# uC.net
KiCad netlist of a schematic drawn in Altium Designer
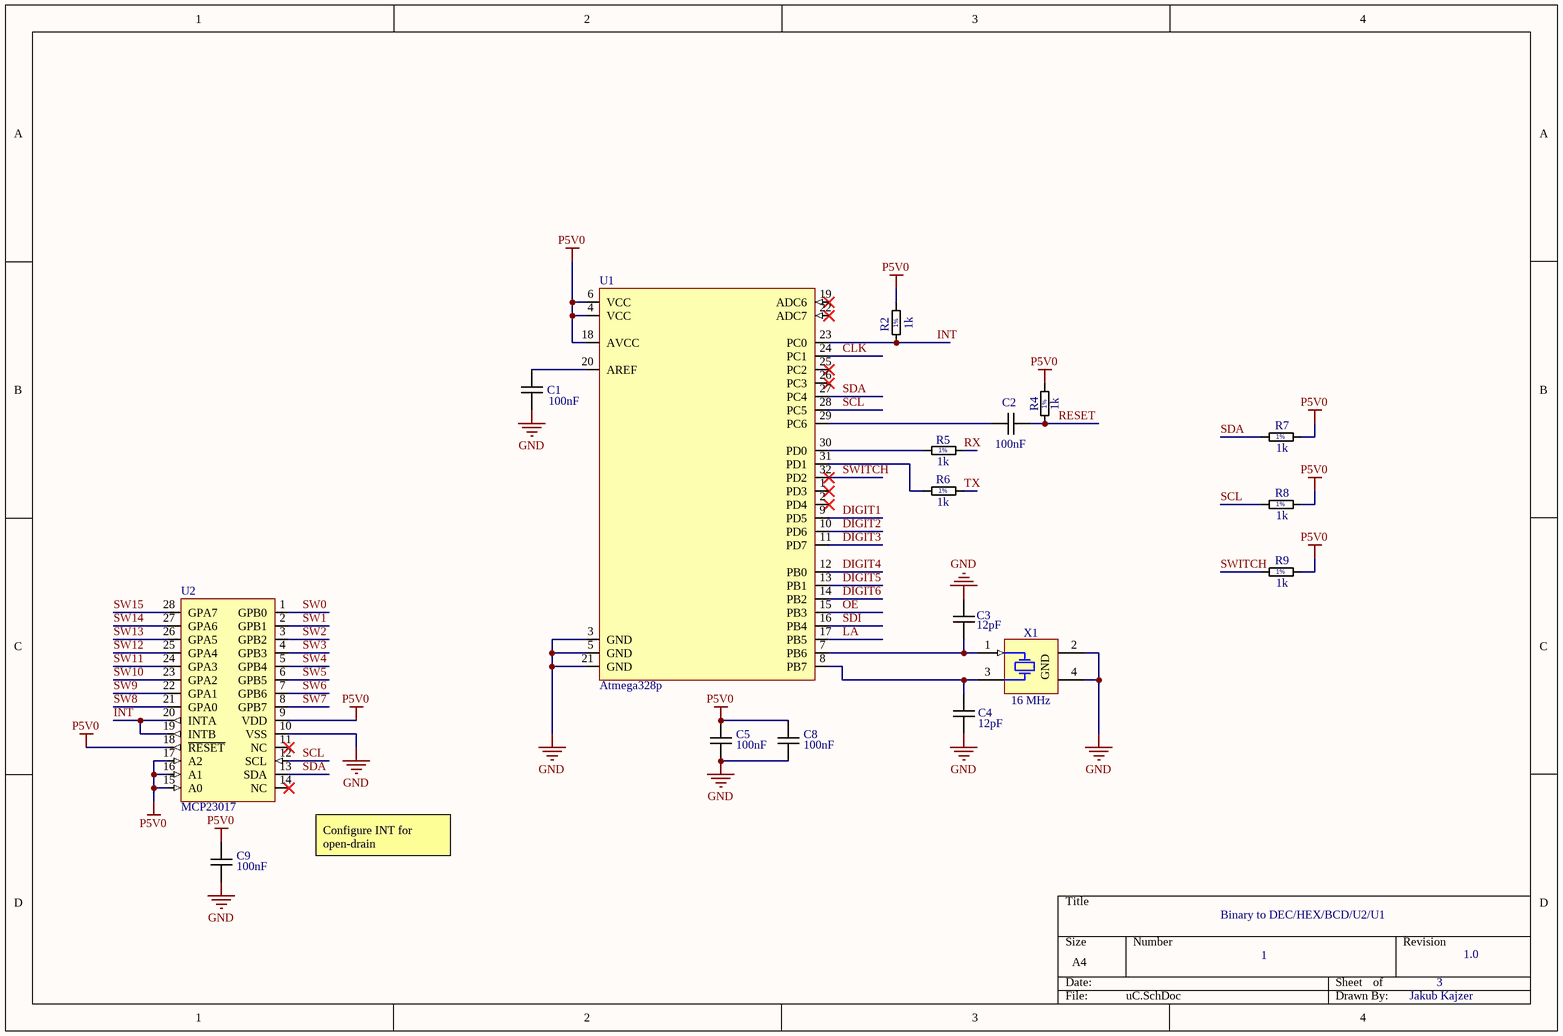
[diagram p0: uC.SchDoc]

(export (version "E")
  (design (tool "Eeschema 10.0.6"))
  (components
    (comp (ref "C1")
      (value "100nF")
      (footprint "CAPC0402X60N")
      (description "Non-polarised capacitor")
      (fields
        (field (name "MANUFACTURER") "GENERIC")
        (field (name "MANUFACTURER PART NUMBER") "CC0402_100NF_16V_10%_X7R")
        (field (name "AUTHOR") "KB")
      )
      (libsource (lib "Capacitors") (part "Capacitor - non polarized"))
    )
    (comp (ref "C2")
      (value "100nF")
      (footprint "CAPC0402X60N")
      (description "Non-polarised capacitor")
      (fields
        (field (name "MANUFACTURER") "GENERIC")
        (field (name "MANUFACTURER PART NUMBER") "CC0402_100NF_16V_10%_X7R")
        (field (name "AUTHOR") "KB")
      )
      (libsource (lib "Capacitors") (part "Capacitor - non polarized"))
    )
    (comp (ref "C3")
      (value "12pF")
      (footprint "CAPC0402X60N")
      (description "Non-polarised capacitor")
      (fields
        (field (name "MANUFACTURER") "GENERIC")
        (field (name "MANUFACTURER PART NUMBER") "CC0402_12PF_50V_5%_C0G")
        (field (name "AUTHOR") "KB")
      )
      (libsource (lib "Capacitors") (part "Capacitor - non polarized"))
    )
    (comp (ref "C4")
      (value "12pF")
      (footprint "CAPC0402X60N")
      (description "Non-polarised capacitor")
      (fields
        (field (name "MANUFACTURER") "GENERIC")
        (field (name "MANUFACTURER PART NUMBER") "CC0402_12PF_50V_5%_C0G")
        (field (name "AUTHOR") "KB")
      )
      (libsource (lib "Capacitors") (part "Capacitor - non polarized"))
    )
    (comp (ref "C5")
      (value "100nF")
      (footprint "CAPC0402X60N")
      (description "Non-polarised capacitor")
      (fields
        (field (name "MANUFACTURER") "GENERIC")
        (field (name "MANUFACTURER PART NUMBER") "CC0402_100NF_16V_10%_X7R")
        (field (name "AUTHOR") "KB")
      )
      (libsource (lib "Capacitors") (part "Capacitor - non polarized"))
    )
    (comp (ref "C8")
      (value "100nF")
      (footprint "CAPC0402X60N")
      (description "Non-polarised capacitor")
      (fields
        (field (name "MANUFACTURER") "GENERIC")
        (field (name "MANUFACTURER PART NUMBER") "CC0402_100NF_16V_10%_X7R")
        (field (name "AUTHOR") "KB")
      )
      (libsource (lib "Capacitors") (part "Capacitor - non polarized"))
    )
    (comp (ref "C9")
      (value "100nF")
      (footprint "CAPC0402X60N")
      (description "Non-polarised capacitor")
      (fields
        (field (name "MANUFACTURER") "GENERIC")
        (field (name "MANUFACTURER PART NUMBER") "CC0402_100NF_16V_10%_X7R")
        (field (name "AUTHOR") "KB")
      )
      (libsource (lib "Capacitors") (part "Capacitor - non polarized"))
    )
    (comp (ref "R2")
      (value "1k")
      (footprint "RESC0402X40N")
      (description "General Purpose Thick Film Chip Resistor")
      (fields
        (field (name "MANUFACTURER") "GENERIC")
        (field (name "MANUFACTURER PART NUMBER") "R0402_1K00_0.0625W 0.1W 0.125W 0.25W 0.5W 1W 0.75W 1W_100PPM")
        (field (name "AUTHOR") "KB")
      )
      (libsource (lib "Resistors") (part "Resistor - 1%"))
    )
    (comp (ref "R4")
      (value "1k")
      (footprint "RESC0402X40N")
      (description "General Purpose Thick Film Chip Resistor")
      (fields
        (field (name "MANUFACTURER") "GENERIC")
        (field (name "MANUFACTURER PART NUMBER") "R0402_1K00_0.0625W 0.1W 0.125W 0.25W 0.5W 1W 0.75W 1W_100PPM")
        (field (name "AUTHOR") "KB")
      )
      (libsource (lib "Resistors") (part "Resistor - 1%"))
    )
    (comp (ref "R5")
      (value "1k")
      (footprint "RESC0402X40N")
      (description "General Purpose Thick Film Chip Resistor")
      (fields
        (field (name "MANUFACTURER") "GENERIC")
        (field (name "MANUFACTURER PART NUMBER") "R0402_1K00_0.0625W 0.1W 0.125W 0.25W 0.5W 1W 0.75W 1W_100PPM")
        (field (name "AUTHOR") "KB")
      )
      (libsource (lib "Resistors") (part "Resistor - 1%"))
    )
    (comp (ref "R6")
      (value "1k")
      (footprint "RESC0402X40N")
      (description "General Purpose Thick Film Chip Resistor")
      (fields
        (field (name "MANUFACTURER") "GENERIC")
        (field (name "MANUFACTURER PART NUMBER") "R0402_1K00_0.0625W 0.1W 0.125W 0.25W 0.5W 1W 0.75W 1W_100PPM")
        (field (name "AUTHOR") "KB")
      )
      (libsource (lib "Resistors") (part "Resistor - 1%"))
    )
    (comp (ref "R7")
      (value "1k")
      (footprint "RESC0402X40N")
      (description "General Purpose Thick Film Chip Resistor")
      (fields
        (field (name "MANUFACTURER") "GENERIC")
        (field (name "MANUFACTURER PART NUMBER") "R0402_1K00_0.0625W 0.1W 0.125W 0.25W 0.5W 1W 0.75W 1W_100PPM")
        (field (name "AUTHOR") "KB")
      )
      (libsource (lib "Resistors") (part "Resistor - 1%"))
    )
    (comp (ref "R8")
      (value "1k")
      (footprint "RESC0402X40N")
      (description "General Purpose Thick Film Chip Resistor")
      (fields
        (field (name "MANUFACTURER") "GENERIC")
        (field (name "MANUFACTURER PART NUMBER") "R0402_1K00_0.0625W 0.1W 0.125W 0.25W 0.5W 1W 0.75W 1W_100PPM")
        (field (name "AUTHOR") "KB")
      )
      (libsource (lib "Resistors") (part "Resistor - 1%"))
    )
    (comp (ref "R9")
      (value "1k")
      (footprint "RESC0402X40N")
      (description "General Purpose Thick Film Chip Resistor")
      (fields
        (field (name "MANUFACTURER") "GENERIC")
        (field (name "MANUFACTURER PART NUMBER") "R0402_1K00_0.0625W 0.1W 0.125W 0.25W 0.5W 1W 0.75W 1W_100PPM")
        (field (name "AUTHOR") "KB")
      )
      (libsource (lib "Resistors") (part "Resistor - 1%"))
    )
    (comp (ref "U1")
      (value "Atmega328p")
      (footprint "STM-LQFP32_N")
      (description "8-bit AVR Microcontroller with 32K Bytes In-SystemProgrammable Flash")
      (fields (field (name "MANUFACTURER 1 PART NUMBER") "ATMEGA328PB-AU") (field (name "AUTHOR") "JK"))
      (libsource (lib "ICs And Semiconductors") (part "Atmega328p"))
    )
    (comp (ref "U2")
      (value "MCP23017")
      (footprint "SSOP28")
      (description "16-Bit I/O Expander with Serial Interface")
      (fields (field (name "MANUFACTURER 1 PART NUMBER") "MCP23017-E/SS") (field (name "AUTHOR") "JK"))
      (libsource (lib "ICs And Semiconductors") (part "MCP23017"))
    )
    (comp (ref "X1")
      (value "16 MHz")
      (footprint "LFXTAL069392CUTT")
      (description "ˇĹ0ppm 10pF -40°C to +85°C  4 Pins, 2.5x2X0.6mm")
      (fields (field (name "MANUFACTURER 1 PART NUMBER") "LFXTAL069392CUTT") (field (name "AUTHOR") "PC"))
      (libsource (lib "ICs And Semiconductors") (part "Quartz Crystal 1X 2GND 3X 4GND"))
    )
  )
  (nets
    (net (code "1") (name "/CLK") (class "Default")
      (node (ref "U1") (pin "24") (pinfunction "PC1_24") (pintype "bidirectional"))
    )
    (net (code "2") (name "/DIGIT1") (class "Default")
      (node (ref "U1") (pin "9") (pinfunction "PD5_9") (pintype "bidirectional"))
    )
    (net (code "3") (name "/DIGIT2") (class "Default")
      (node (ref "U1") (pin "10") (pinfunction "PD6_10") (pintype "bidirectional"))
    )
    (net (code "4") (name "/DIGIT3") (class "Default")
      (node (ref "U1") (pin "11") (pinfunction "PD7_11") (pintype "bidirectional"))
    )
    (net (code "5") (name "/DIGIT4") (class "Default")
      (node (ref "U1") (pin "12") (pinfunction "PB0_12") (pintype "bidirectional"))
    )
    (net (code "6") (name "/DIGIT5") (class "Default")
      (node (ref "U1") (pin "13") (pinfunction "PB1_13") (pintype "bidirectional"))
    )
    (net (code "7") (name "/DIGIT6") (class "Default")
      (node (ref "U1") (pin "14") (pinfunction "PB2_14") (pintype "bidirectional"))
    )
    (net (code "8") (name "/INT") (class "Default")
      (node (ref "R2") (pin "1") (pinfunction "1_1") (pintype "passive"))
      (node (ref "U1") (pin "23") (pinfunction "PC0_23") (pintype "bidirectional"))
      (node (ref "U2") (pin "19") (pinfunction "INTB_19") (pintype "output"))
      (node (ref "U2") (pin "20") (pinfunction "INTA_20") (pintype "output"))
    )
    (net (code "9") (name "/LA") (class "Default")
      (node (ref "U1") (pin "17") (pinfunction "PB5_17") (pintype "bidirectional"))
    )
    (net (code "10") (name "/OE") (class "Default")
      (node (ref "U1") (pin "15") (pinfunction "PB3_15") (pintype "bidirectional"))
    )
    (net (code "11") (name "/RESET") (class "Default")
      (node (ref "C2") (pin "2") (pinfunction "2_2") (pintype "passive"))
      (node (ref "R4") (pin "1") (pinfunction "1_1") (pintype "passive"))
    )
    (net (code "12") (name "/RX") (class "Default")
      (node (ref "R5") (pin "2") (pinfunction "2_2") (pintype "passive"))
    )
    (net (code "13") (name "/SCL") (class "Default")
      (node (ref "R8") (pin "1") (pinfunction "1_1") (pintype "passive"))
      (node (ref "U1") (pin "28") (pinfunction "PC5_28") (pintype "bidirectional"))
      (node (ref "U2") (pin "12") (pinfunction "SCL_12") (pintype "input"))
    )
    (net (code "14") (name "/SDA") (class "Default")
      (node (ref "R7") (pin "1") (pinfunction "1_1") (pintype "passive"))
      (node (ref "U1") (pin "27") (pinfunction "PC4_27") (pintype "bidirectional"))
      (node (ref "U2") (pin "13") (pinfunction "SDA_13") (pintype "bidirectional"))
    )
    (net (code "15") (name "/SDI") (class "Default")
      (node (ref "U1") (pin "16") (pinfunction "PB4_16") (pintype "bidirectional"))
    )
    (net (code "16") (name "/SW0") (class "Default")
      (node (ref "U2") (pin "1") (pinfunction "GPB0_1") (pintype "bidirectional"))
    )
    (net (code "17") (name "/SW1") (class "Default")
      (node (ref "U2") (pin "2") (pinfunction "GPB1_2") (pintype "bidirectional"))
    )
    (net (code "18") (name "/SW2") (class "Default")
      (node (ref "U2") (pin "3") (pinfunction "GPB2_3") (pintype "bidirectional"))
    )
    (net (code "19") (name "/SW3") (class "Default")
      (node (ref "U2") (pin "4") (pinfunction "GPB3_4") (pintype "bidirectional"))
    )
    (net (code "20") (name "/SW4") (class "Default")
      (node (ref "U2") (pin "5") (pinfunction "GPB4_5") (pintype "bidirectional"))
    )
    (net (code "21") (name "/SW5") (class "Default")
      (node (ref "U2") (pin "6") (pinfunction "GPB5_6") (pintype "bidirectional"))
    )
    (net (code "22") (name "/SW6") (class "Default")
      (node (ref "U2") (pin "7") (pinfunction "GPB6_7") (pintype "bidirectional"))
    )
    (net (code "23") (name "/SW7") (class "Default")
      (node (ref "U2") (pin "8") (pinfunction "GPB7_8") (pintype "bidirectional"))
    )
    (net (code "24") (name "/SW8") (class "Default")
      (node (ref "U2") (pin "21") (pinfunction "GPA0_21") (pintype "bidirectional"))
    )
    (net (code "25") (name "/SW9") (class "Default")
      (node (ref "U2") (pin "22") (pinfunction "GPA1_22") (pintype "bidirectional"))
    )
    (net (code "26") (name "/SW10") (class "Default")
      (node (ref "U2") (pin "23") (pinfunction "GPA2_23") (pintype "bidirectional"))
    )
    (net (code "27") (name "/SW11") (class "Default")
      (node (ref "U2") (pin "24") (pinfunction "GPA3_24") (pintype "bidirectional"))
    )
    (net (code "28") (name "/SW12") (class "Default")
      (node (ref "U2") (pin "25") (pinfunction "GPA4_25") (pintype "bidirectional"))
    )
    (net (code "29") (name "/SW13") (class "Default")
      (node (ref "U2") (pin "26") (pinfunction "GPA5_26") (pintype "bidirectional"))
    )
    (net (code "30") (name "/SW14") (class "Default")
      (node (ref "U2") (pin "27") (pinfunction "GPA6_27") (pintype "bidirectional"))
    )
    (net (code "31") (name "/SW15") (class "Default")
      (node (ref "U2") (pin "28") (pinfunction "GPA7_28") (pintype "bidirectional"))
    )
    (net (code "32") (name "/SWITCH") (class "Default")
      (node (ref "R9") (pin "1") (pinfunction "1_1") (pintype "passive"))
      (node (ref "U1") (pin "32") (pinfunction "PD2_32") (pintype "bidirectional"))
    )
    (net (code "33") (name "/TX") (class "Default")
      (node (ref "R6") (pin "2") (pinfunction "2_2") (pintype "passive"))
    )
    (net (code "34") (name "GND") (class "Default")
      (node (ref "C1") (pin "1") (pinfunction "1_1") (pintype "passive"))
      (node (ref "C3") (pin "2") (pinfunction "2_2") (pintype "passive"))
      (node (ref "C4") (pin "1") (pinfunction "1_1") (pintype "passive"))
      (node (ref "C5") (pin "1") (pinfunction "1_1") (pintype "passive"))
      (node (ref "C8") (pin "1") (pinfunction "1_1") (pintype "passive"))
      (node (ref "C9") (pin "1") (pinfunction "1_1") (pintype "passive"))
      (node (ref "U1") (pin "21") (pinfunction "GND_21") (pintype "power_in"))
      (node (ref "U1") (pin "3") (pinfunction "GND_3") (pintype "power_in"))
      (node (ref "U1") (pin "5") (pinfunction "GND_5") (pintype "power_in"))
      (node (ref "U2") (pin "10") (pinfunction "VSS_10") (pintype "power_in"))
      (node (ref "X1") (pin "2") (pinfunction "GND_2") (pintype "power_in"))
      (node (ref "X1") (pin "4") (pinfunction "GND_4") (pintype "power_in"))
    )
    (net (code "35") (name "Net-(U1-AREF)") (class "Default")
      (node (ref "C1") (pin "2") (pinfunction "2_2") (pintype "passive"))
      (node (ref "U1") (pin "20") (pinfunction "AREF_20") (pintype "power_in"))
    )
    (net (code "36") (name "Net-(U1-PB6)") (class "Default")
      (node (ref "C3") (pin "1") (pinfunction "1_1") (pintype "passive"))
      (node (ref "U1") (pin "7") (pinfunction "PB6_7") (pintype "bidirectional"))
      (node (ref "X1") (pin "1") (pinfunction "X_1") (pintype "input"))
    )
    (net (code "37") (name "Net-(U1-PB7)") (class "Default")
      (node (ref "C4") (pin "2") (pinfunction "2_2") (pintype "passive"))
      (node (ref "U1") (pin "8") (pinfunction "PB7_8") (pintype "bidirectional"))
      (node (ref "X1") (pin "3") (pinfunction "X_3") (pintype "power_in"))
    )
    (net (code "38") (name "Net-(U1-PC6)") (class "Default")
      (node (ref "C2") (pin "1") (pinfunction "1_1") (pintype "passive"))
      (node (ref "U1") (pin "29") (pinfunction "PC6_29") (pintype "bidirectional"))
    )
    (net (code "39") (name "Net-(U1-PD0)") (class "Default")
      (node (ref "R5") (pin "1") (pinfunction "1_1") (pintype "passive"))
      (node (ref "U1") (pin "30") (pinfunction "PD0_30") (pintype "bidirectional"))
    )
    (net (code "40") (name "Net-(U1-PD1)") (class "Default")
      (node (ref "R6") (pin "1") (pinfunction "1_1") (pintype "passive"))
      (node (ref "U1") (pin "31") (pinfunction "PD1_31") (pintype "bidirectional"))
    )
    (net (code "41") (name "P5V0") (class "Default")
      (node (ref "C5") (pin "2") (pinfunction "2_2") (pintype "passive"))
      (node (ref "C8") (pin "2") (pinfunction "2_2") (pintype "passive"))
      (node (ref "C9") (pin "2") (pinfunction "2_2") (pintype "passive"))
      (node (ref "R2") (pin "2") (pinfunction "2_2") (pintype "passive"))
      (node (ref "R4") (pin "2") (pinfunction "2_2") (pintype "passive"))
      (node (ref "R7") (pin "2") (pinfunction "2_2") (pintype "passive"))
      (node (ref "R8") (pin "2") (pinfunction "2_2") (pintype "passive"))
      (node (ref "R9") (pin "2") (pinfunction "2_2") (pintype "passive"))
      (node (ref "U1") (pin "18") (pinfunction "AVCC_18") (pintype "power_in"))
      (node (ref "U1") (pin "4") (pinfunction "VCC_4") (pintype "power_in"))
      (node (ref "U1") (pin "6") (pinfunction "VCC_6") (pintype "power_in"))
      (node (ref "U2") (pin "15") (pinfunction "A0_15") (pintype "input"))
      (node (ref "U2") (pin "16") (pinfunction "A1_16") (pintype "input"))
      (node (ref "U2") (pin "17") (pinfunction "A2_17") (pintype "input"))
      (node (ref "U2") (pin "18") (pinfunction "~{RESET}_18") (pintype "output"))
      (node (ref "U2") (pin "9") (pinfunction "VDD_9") (pintype "power_in"))
    )
    (net (code "42") (name "unconnected-(U1-ADC6-Pad19)") (class "Default")
      (node (ref "U1") (pin "19") (pinfunction "ADC6_19") (pintype "input+no_connect"))
    )
    (net (code "43") (name "unconnected-(U1-ADC7-Pad22)") (class "Default")
      (node (ref "U1") (pin "22") (pinfunction "ADC7_22") (pintype "input+no_connect"))
    )
    (net (code "44") (name "unconnected-(U1-PC2-Pad25)") (class "Default")
      (node (ref "U1") (pin "25") (pinfunction "PC2_25") (pintype "bidirectional+no_connect"))
    )
    (net (code "45") (name "unconnected-(U1-PC3-Pad26)") (class "Default")
      (node (ref "U1") (pin "26") (pinfunction "PC3_26") (pintype "bidirectional+no_connect"))
    )
    (net (code "46") (name "unconnected-(U1-PD3-Pad1)") (class "Default")
      (node (ref "U1") (pin "1") (pinfunction "PD3_1") (pintype "bidirectional+no_connect"))
    )
    (net (code "47") (name "unconnected-(U1-PD4-Pad2)") (class "Default")
      (node (ref "U1") (pin "2") (pinfunction "PD4_2") (pintype "bidirectional+no_connect"))
    )
    (net (code "48") (name "unconnected-(U2-NC-Pad11)") (class "Default")
      (node (ref "U2") (pin "11") (pinfunction "NC_11") (pintype "passive+no_connect"))
    )
    (net (code "49") (name "unconnected-(U2-NC-Pad14)") (class "Default")
      (node (ref "U2") (pin "14") (pinfunction "NC_14") (pintype "passive+no_connect"))
    )
  )
)
